# middleboard.net
KiCad netlist of a schematic drawn in EAGLE
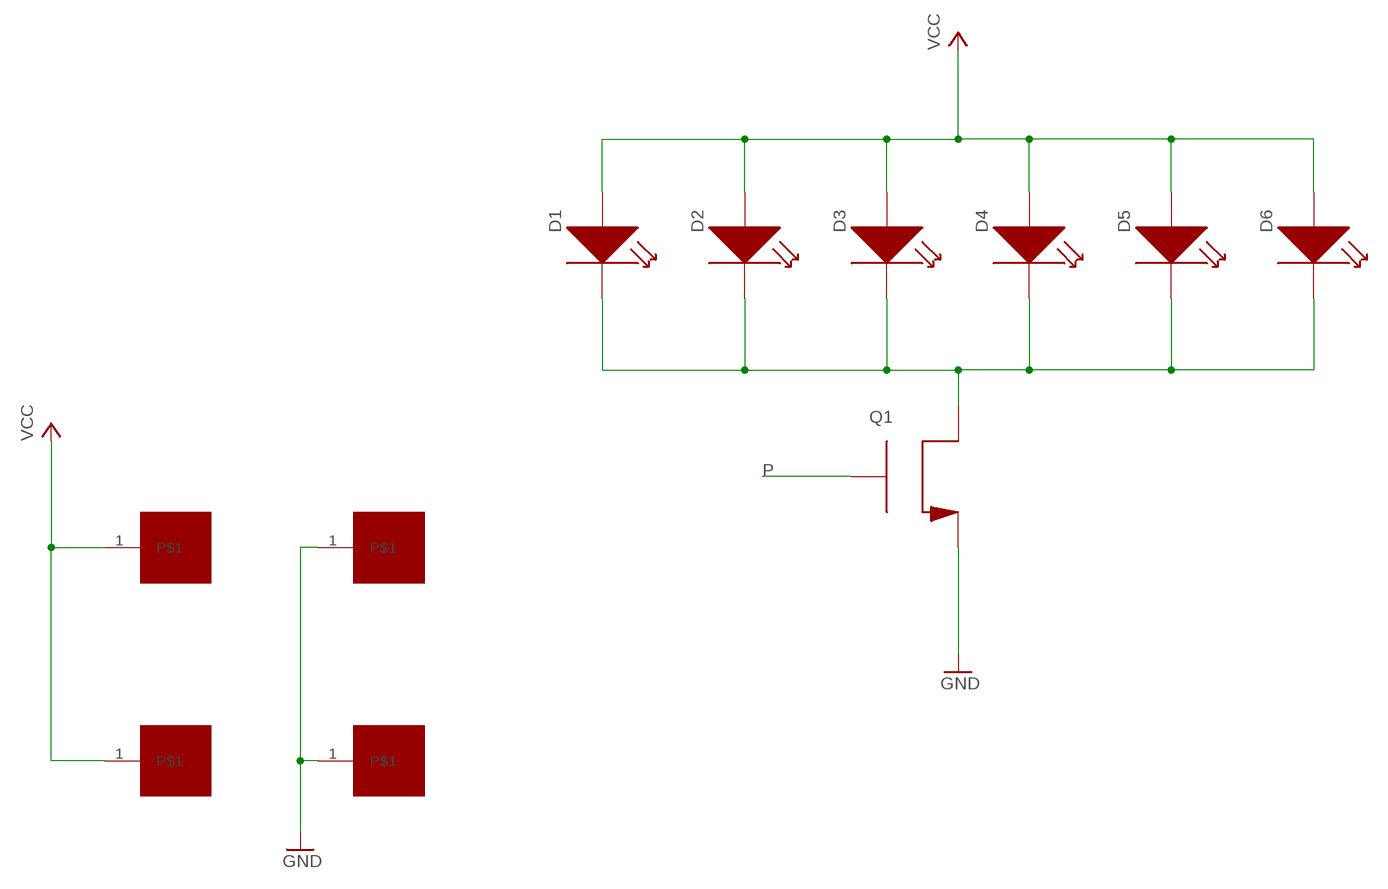
[diagram p0: schematic, sheet 1]

(export (version "E")
  (design (tool "Eeschema 10.0.6"))
  (components
    (comp (ref "D1")
      (value "NVSLE21AT")
      (footprint "eagle-import:NVSLE21AT")
      (libsource (lib "eagle-import") (part "NVSLE21AT"))
    )
    (comp (ref "D2")
      (value "NVSLE21AT")
      (footprint "eagle-import:NVSLE21AT")
      (libsource (lib "eagle-import") (part "NVSLE21AT"))
    )
    (comp (ref "D3")
      (value "NVSLE21AT")
      (footprint "eagle-import:NVSLE21AT")
      (libsource (lib "eagle-import") (part "NVSLE21AT"))
    )
    (comp (ref "D4")
      (value "NVSLE21AT")
      (footprint "eagle-import:NVSLE21AT")
      (libsource (lib "eagle-import") (part "NVSLE21AT"))
    )
    (comp (ref "D5")
      (value "NVSLE21AT")
      (footprint "eagle-import:NVSLE21AT")
      (libsource (lib "eagle-import") (part "NVSLE21AT"))
    )
    (comp (ref "D6")
      (value "NVSLE21AT")
      (footprint "eagle-import:NVSLE21AT")
      (libsource (lib "eagle-import") (part "NVSLE21AT"))
    )
    (comp (ref "P1")
      (value "PAD")
      (footprint "eagle-import:PAD")
      (libsource (lib "eagle-import") (part "PAD"))
    )
    (comp (ref "P2")
      (value "PAD")
      (footprint "eagle-import:PAD")
      (libsource (lib "eagle-import") (part "PAD"))
    )
    (comp (ref "P3")
      (value "PAD")
      (footprint "eagle-import:PAD")
      (libsource (lib "eagle-import") (part "PAD"))
    )
    (comp (ref "P4")
      (value "PAD")
      (footprint "eagle-import:PAD")
      (libsource (lib "eagle-import") (part "PAD"))
    )
    (comp (ref "Q1")
      (value "SIA436DJ")
      (footprint "eagle-import:POWERPAK_SC70-6L")
      (libsource (lib "eagle-import") (part "SIA436DJ"))
    )
  )
  (nets
    (net (code "1") (name "/P") (class "Default")
      (node (ref "Q1") (pin "P$4") (pinfunction "G_P$4") (pintype "bidirectional"))
    )
    (net (code "2") (name "GND") (class "Default")
      (node (ref "P2") (pin "1") (pinfunction "P$1_1") (pintype "bidirectional"))
      (node (ref "P3") (pin "1") (pinfunction "P$1_1") (pintype "bidirectional"))
      (node (ref "Q1") (pin "P$2") (pinfunction "S_P$2") (pintype "bidirectional"))
      (node (ref "Q1") (pin "P$3") (pinfunction "S_P$3") (pintype "bidirectional"))
    )
    (net (code "3") (name "Net-(D1-CATHODE)") (class "Default")
      (node (ref "D1") (pin "P$1") (pinfunction "CATHODE_P$1") (pintype "bidirectional"))
      (node (ref "D2") (pin "P$1") (pinfunction "CATHODE_P$1") (pintype "bidirectional"))
      (node (ref "D3") (pin "P$1") (pinfunction "CATHODE_P$1") (pintype "bidirectional"))
      (node (ref "D4") (pin "P$1") (pinfunction "CATHODE_P$1") (pintype "bidirectional"))
      (node (ref "D5") (pin "P$1") (pinfunction "CATHODE_P$1") (pintype "bidirectional"))
      (node (ref "D6") (pin "P$1") (pinfunction "CATHODE_P$1") (pintype "bidirectional"))
      (node (ref "Q1") (pin "P$1") (pinfunction "D_P$1") (pintype "bidirectional"))
      (node (ref "Q1") (pin "P$5") (pinfunction "D_P$5") (pintype "bidirectional"))
      (node (ref "Q1") (pin "P$6") (pinfunction "D_P$6") (pintype "bidirectional"))
      (node (ref "Q1") (pin "P$7") (pinfunction "D_P$7") (pintype "bidirectional"))
      (node (ref "Q1") (pin "P$8") (pinfunction "D_P$8") (pintype "bidirectional"))
    )
    (net (code "4") (name "VCC") (class "Default")
      (node (ref "D1") (pin "P$2") (pinfunction "ANODE_P$2") (pintype "bidirectional"))
      (node (ref "D2") (pin "P$2") (pinfunction "ANODE_P$2") (pintype "bidirectional"))
      (node (ref "D3") (pin "P$2") (pinfunction "ANODE_P$2") (pintype "bidirectional"))
      (node (ref "D4") (pin "P$2") (pinfunction "ANODE_P$2") (pintype "bidirectional"))
      (node (ref "D5") (pin "P$2") (pinfunction "ANODE_P$2") (pintype "bidirectional"))
      (node (ref "D6") (pin "P$2") (pinfunction "ANODE_P$2") (pintype "bidirectional"))
      (node (ref "P1") (pin "1") (pinfunction "P$1_1") (pintype "bidirectional"))
      (node (ref "P4") (pin "1") (pinfunction "P$1_1") (pintype "bidirectional"))
    )
  )
)
